# Adafruit_Feather_nRF52840_Sense_Rev_C.net
KiCad netlist of a schematic drawn in EAGLE
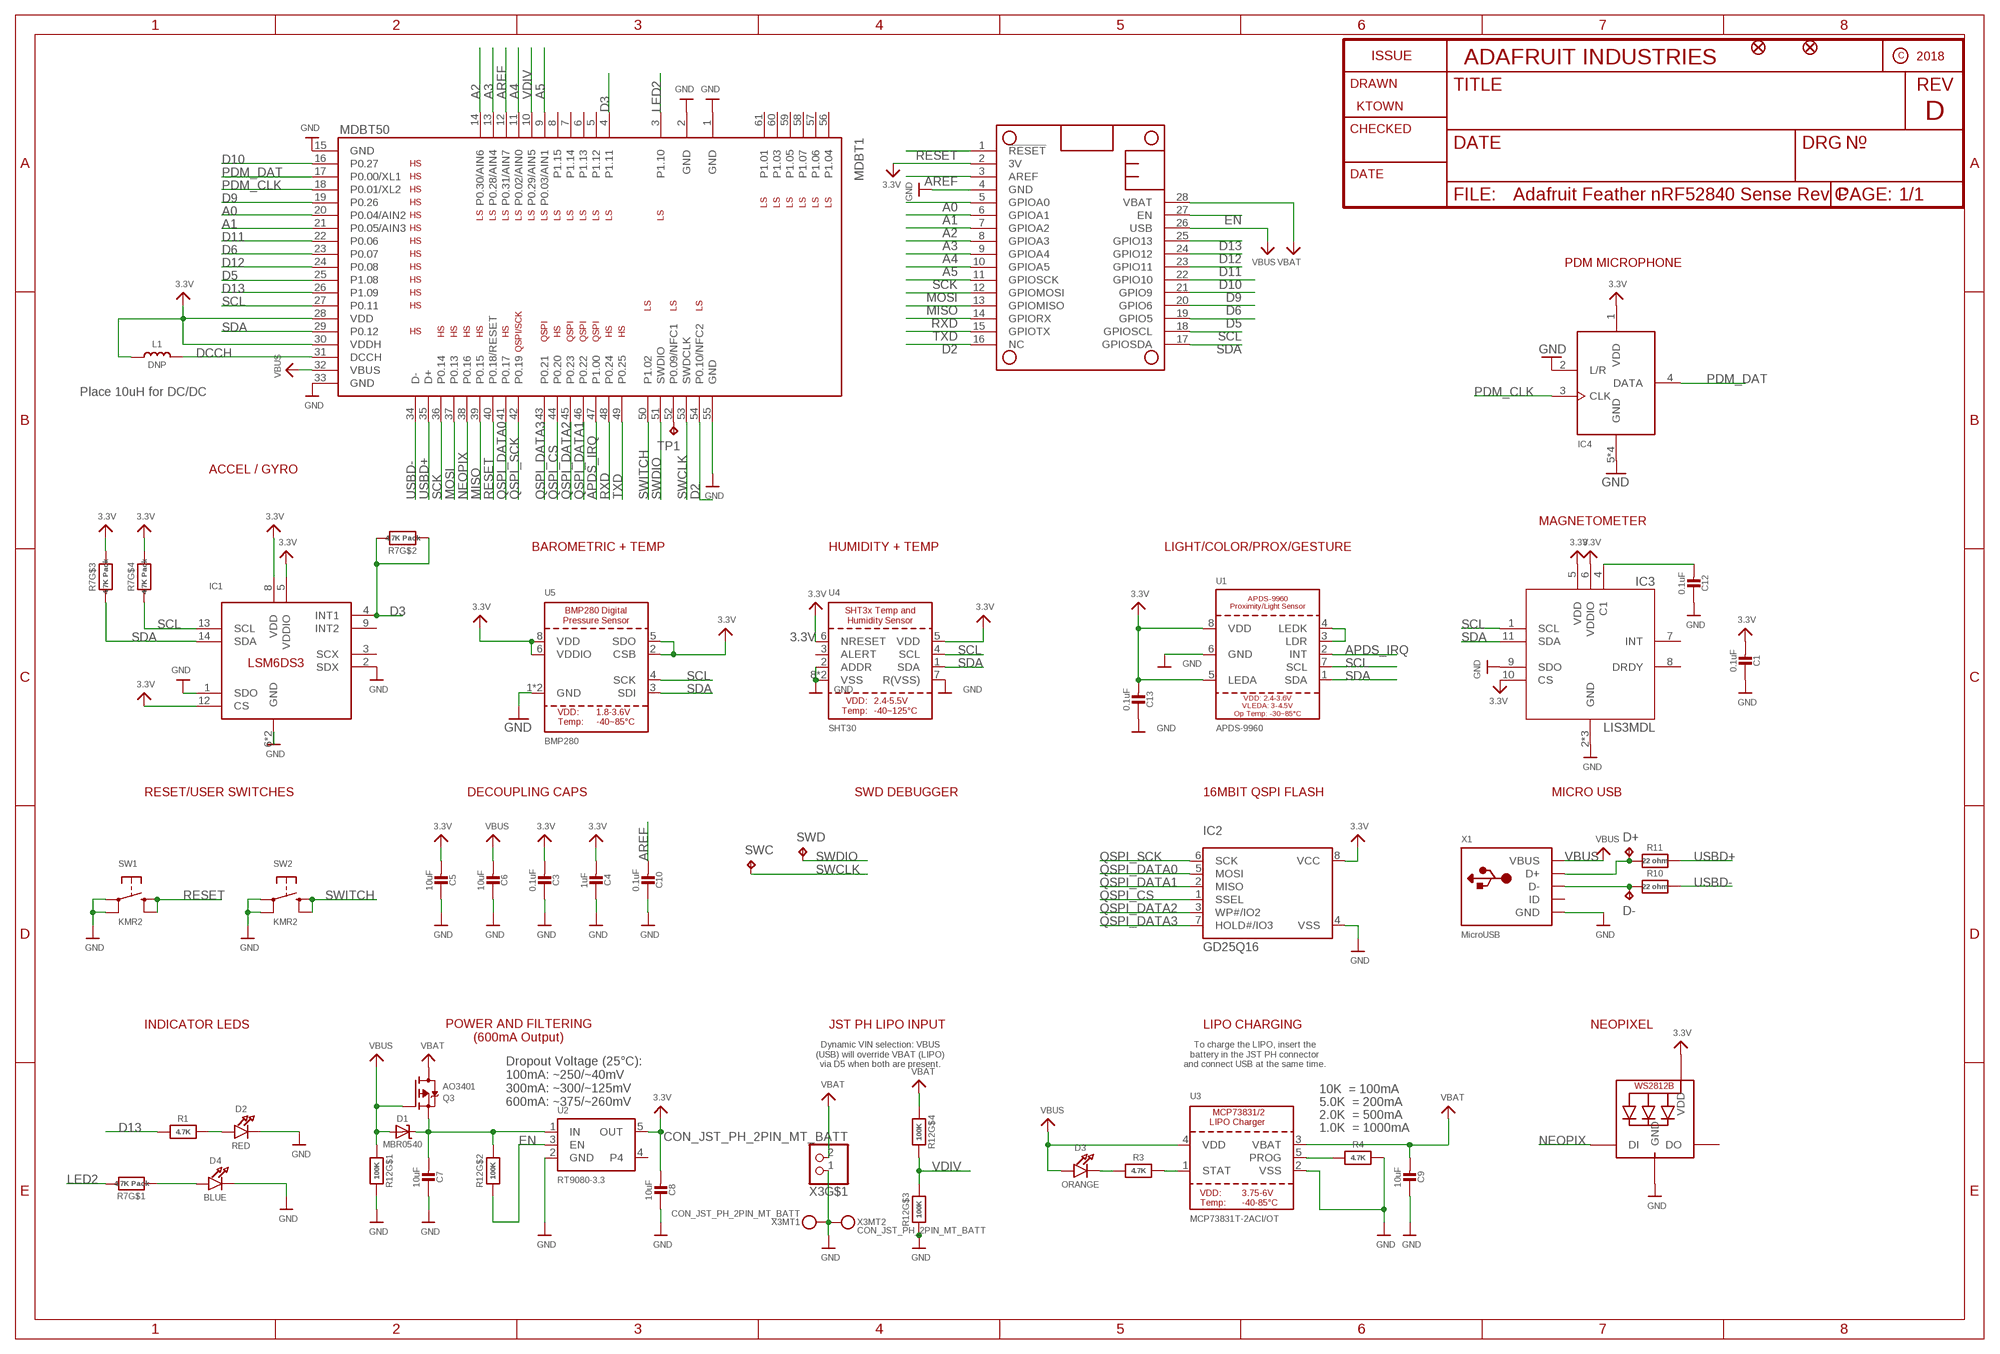
[diagram p0: schematic, sheet 1]

(export (version "E")
  (design (tool "Eeschema 10.0.6"))
  (components
    (comp (ref "C1")
      (value "0.1uF")
      (footprint "eagle-import:0603-NO")
      (libsource (lib "eagle-import") (part "CAP_CERAMIC0603_NO"))
    )
    (comp (ref "C3")
      (value "0.1uF")
      (footprint "eagle-import:0603-NO")
      (libsource (lib "eagle-import") (part "CAP_CERAMIC0603_NO"))
    )
    (comp (ref "C4")
      (value "1uF")
      (footprint "eagle-import:0603-NO")
      (libsource (lib "eagle-import") (part "CAP_CERAMIC0603_NO"))
    )
    (comp (ref "C5")
      (value "10uF")
      (footprint "eagle-import:0805-NO")
      (libsource (lib "eagle-import") (part "CAP_CERAMIC0805-NOOUTLINE"))
    )
    (comp (ref "C6")
      (value "10uF")
      (footprint "eagle-import:0805-NO")
      (libsource (lib "eagle-import") (part "CAP_CERAMIC0805-NOOUTLINE"))
    )
    (comp (ref "C7")
      (value "10uF")
      (footprint "eagle-import:0805-NO")
      (libsource (lib "eagle-import") (part "CAP_CERAMIC0805-NOOUTLINE"))
    )
    (comp (ref "C8")
      (value "10uF")
      (footprint "eagle-import:0805-NO")
      (libsource (lib "eagle-import") (part "CAP_CERAMIC0805-NOOUTLINE"))
    )
    (comp (ref "C9")
      (value "10uF")
      (footprint "eagle-import:0805-NO")
      (libsource (lib "eagle-import") (part "CAP_CERAMIC0805-NOOUTLINE"))
    )
    (comp (ref "C10")
      (value "0.1uF")
      (footprint "eagle-import:0603-NO")
      (libsource (lib "eagle-import") (part "CAP_CERAMIC0603_NO"))
    )
    (comp (ref "C12")
      (value "0.1uF")
      (footprint "eagle-import:0603-NO")
      (libsource (lib "eagle-import") (part "CAP_CERAMIC0603_NO"))
    )
    (comp (ref "C13")
      (value "0.1uF")
      (footprint "eagle-import:0603-NO")
      (libsource (lib "eagle-import") (part "CAP_CERAMIC0603_NO"))
    )
    (comp (ref "D+")
      (value "TPTP10R")
      (footprint "eagle-import:TP10R")
      (libsource (lib "eagle-import") (part "TPTP10R"))
    )
    (comp (ref "D-")
      (value "TPTP10R")
      (footprint "eagle-import:TP10R")
      (libsource (lib "eagle-import") (part "TPTP10R"))
    )
    (comp (ref "D1")
      (value "MBR0540")
      (footprint "eagle-import:SOD-123")
      (libsource (lib "eagle-import") (part "DIODE-SCHOTTKYSOD-123"))
    )
    (comp (ref "D2")
      (value "RED")
      (footprint "eagle-import:CHIPLED_0603_NOOUTLINE")
      (libsource (lib "eagle-import") (part "LED0603_NOOUTLINE"))
    )
    (comp (ref "D3")
      (value "ORANGE")
      (footprint "eagle-import:CHIPLED_0603_NOOUTLINE")
      (libsource (lib "eagle-import") (part "LED0603_NOOUTLINE"))
    )
    (comp (ref "D4")
      (value "BLUE")
      (footprint "eagle-import:CHIPLED_0603_NOOUTLINE")
      (libsource (lib "eagle-import") (part "LED0603_NOOUTLINE"))
    )
    (comp (ref "FID1")
      (value "FIDUCIAL_1MM")
      (footprint "eagle-import:FIDUCIAL_1MM")
      (libsource (lib "eagle-import") (part "FIDUCIAL_1MM"))
    )
    (comp (ref "FID2")
      (value "FIDUCIAL_1MM")
      (footprint "eagle-import:FIDUCIAL_1MM")
      (libsource (lib "eagle-import") (part "FIDUCIAL_1MM"))
    )
    (comp (ref "IC1")
      (value "LSM6DS3")
      (footprint "eagle-import:LGA-14L")
      (libsource (lib "eagle-import") (part "LSM6DS3"))
    )
    (comp (ref "IC2")
      (value "GD25Q16")
      (footprint "eagle-import:USON8")
      (libsource (lib "eagle-import") (part "SPIFLASH_8PINUX"))
    )
    (comp (ref "IC3")
      (value "LIS3MDL")
      (footprint "eagle-import:LGA12_2X2MM")
      (libsource (lib "eagle-import") (part "LIS3MDL"))
    )
    (comp (ref "IC4")
      (value "MIC_PDM")
      (footprint "eagle-import:SPK0415HM4H")
      (libsource (lib "eagle-import") (part "MIC_PDM_SPK0415"))
    )
    (comp (ref "L1")
      (value "DNP")
      (footprint "eagle-import:_0805MP")
      (libsource (lib "eagle-import") (part "INDUCTOR_0805MP"))
    )
    (comp (ref "LED1")
      (value "WS2812B_3535FULL")
      (footprint "eagle-import:LED3535_FULLPADS")
      (libsource (lib "eagle-import") (part "WS2812B_3535FULL"))
    )
    (comp (ref "MDBT1")
      (value "MDBT50")
      (footprint "eagle-import:MDBT50")
      (libsource (lib "eagle-import") (part "MDBT50"))
    )
    (comp (ref "MS1")
      (value "FEATHERWING_NODIM")
      (footprint "eagle-import:FEATHERWING_NODIM")
      (libsource (lib "eagle-import") (part "FEATHERWING_NODIM"))
    )
    (comp (ref "Q3")
      (value "AO3401")
      (footprint "eagle-import:SOT23-R")
      (libsource (lib "eagle-import") (part "MOSFET-P"))
    )
    (comp (ref "R1")
      (value "4.7K")
      (footprint "eagle-import:0603-NO")
      (libsource (lib "eagle-import") (part "RESISTOR_0603_NOOUT"))
    )
    (comp (ref "R3")
      (value "4.7K")
      (footprint "eagle-import:0603-NO")
      (libsource (lib "eagle-import") (part "RESISTOR_0603_NOOUT"))
    )
    (comp (ref "R4")
      (value "4.7K")
      (footprint "eagle-import:0603-NO")
      (libsource (lib "eagle-import") (part "RESISTOR_0603_NOOUT"))
    )
    (comp (ref "R7")
      (value "4.7K Pack")
      (footprint "eagle-import:RESPACK_4X0603")
      (libsource (lib "eagle-import") (part "RESISTOR_4PACK"))
    )
    (comp (ref "R10")
      (value "22 ohm")
      (footprint "eagle-import:0603-NO")
      (libsource (lib "eagle-import") (part "RESISTOR_0603_NOOUT"))
    )
    (comp (ref "R11")
      (value "22 ohm")
      (footprint "eagle-import:0603-NO")
      (libsource (lib "eagle-import") (part "RESISTOR_0603_NOOUT"))
    )
    (comp (ref "R12")
      (value "100K")
      (footprint "eagle-import:RESPACK_4X0603")
      (libsource (lib "eagle-import") (part "RESISTOR_4PACK"))
    )
    (comp (ref "SW1")
      (value "KMR2")
      (footprint "eagle-import:BTN_RKB2_4.6X2.8")
      (libsource (lib "eagle-import") (part "SWITCH_TACT_SMT_RKB2"))
    )
    (comp (ref "SW2")
      (value "KMR2")
      (footprint "eagle-import:BTN_RKB2_4.6X2.8")
      (libsource (lib "eagle-import") (part "SWITCH_TACT_SMT_RKB2"))
    )
    (comp (ref "SWC")
      (value "TPTP12R")
      (footprint "eagle-import:TP12R")
      (libsource (lib "eagle-import") (part "TPTP12R"))
    )
    (comp (ref "SWD")
      (value "TPTP12R")
      (footprint "eagle-import:TP12R")
      (libsource (lib "eagle-import") (part "TPTP12R"))
    )
    (comp (ref "TP1")
      (value "TPTP10R")
      (footprint "eagle-import:TP10R")
      (libsource (lib "eagle-import") (part "TPTP10R"))
    )
    (comp (ref "U1")
      (value "APDS-9960")
      (footprint "eagle-import:APDS-9960")
      (libsource (lib "eagle-import") (part "APDS-9960"))
    )
    (comp (ref "U2")
      (value "RT9080-3.3")
      (footprint "eagle-import:SOT23-5")
      (fields (field (name "JLC_ROTATION") "0"))
      (libsource (lib "eagle-import") (part "VREG_SOT23-5"))
    )
    (comp (ref "U3")
      (value "MCP73831T-2ACI/OT")
      (footprint "eagle-import:SOT23-5")
      (libsource (lib "eagle-import") (part "MCP73831/2"))
    )
    (comp (ref "U4")
      (value "SHT30")
      (footprint "eagle-import:SHT3X")
      (libsource (lib "eagle-import") (part "SHT3X"))
    )
    (comp (ref "U5")
      (value "BMP280")
      (footprint "eagle-import:BMP280")
      (libsource (lib "eagle-import") (part "BMP280"))
    )
    (comp (ref "X1")
      (value "MicroUSB")
      (footprint "eagle-import:4UCONN_20329_V2")
      (libsource (lib "eagle-import") (part "USB_MICRO_20329_V2"))
    )
    (comp (ref "X3")
      (value "CON_JST_PH_2PIN_MT_BATT")
      (footprint "eagle-import:JSTPH2_BATT")
      (libsource (lib "eagle-import") (part "CON_JST_PH_2PIN_MT_BATT"))
    )
  )
  (nets
    (net (code "1") (name "/A0") (class "Default")
      (node (ref "MDBT1") (pin "20") (pinfunction "P0.04/AIN2_20") (pintype "bidirectional"))
      (node (ref "MS1") (pin "5") (pinfunction "GPIOA0_5") (pintype "bidirectional"))
    )
    (net (code "2") (name "/A1") (class "Default")
      (node (ref "MDBT1") (pin "21") (pinfunction "P0.05/AIN3_21") (pintype "bidirectional"))
      (node (ref "MS1") (pin "6") (pinfunction "GPIOA1_6") (pintype "bidirectional"))
    )
    (net (code "3") (name "/A2") (class "Default")
      (node (ref "MDBT1") (pin "14") (pinfunction "P0.30/AIN6_14") (pintype "bidirectional"))
      (node (ref "MS1") (pin "7") (pinfunction "GPIOA2_7") (pintype "bidirectional"))
    )
    (net (code "4") (name "/A3") (class "Default")
      (node (ref "MDBT1") (pin "13") (pinfunction "P0.28/AIN4_13") (pintype "bidirectional"))
      (node (ref "MS1") (pin "8") (pinfunction "GPIOA3_8") (pintype "bidirectional"))
    )
    (net (code "5") (name "/A4") (class "Default")
      (node (ref "MDBT1") (pin "11") (pinfunction "P0.02/AIN0_11") (pintype "bidirectional"))
      (node (ref "MS1") (pin "9") (pinfunction "GPIOA4_9") (pintype "bidirectional"))
    )
    (net (code "6") (name "/A5") (class "Default")
      (node (ref "MDBT1") (pin "9") (pinfunction "P0.03/AIN1_9") (pintype "bidirectional"))
      (node (ref "MS1") (pin "10") (pinfunction "GPIOA5_10") (pintype "bidirectional"))
    )
    (net (code "7") (name "/APDS_IRQ") (class "Default")
      (node (ref "MDBT1") (pin "47") (pinfunction "P1.00_47") (pintype "bidirectional"))
      (node (ref "U1") (pin "2") (pinfunction "INT_2") (pintype "output"))
    )
    (net (code "8") (name "/AREF") (class "Default")
      (node (ref "C10") (pin "2") (pinfunction "2_2") (pintype "passive"))
      (node (ref "MDBT1") (pin "12") (pinfunction "P0.31/AIN7_12") (pintype "bidirectional"))
      (node (ref "MS1") (pin "3") (pinfunction "AREF_3") (pintype "passive"))
    )
    (net (code "9") (name "/D2") (class "Default")
      (node (ref "MDBT1") (pin "54") (pinfunction "P0.10/NFC2_54") (pintype "bidirectional"))
      (node (ref "MS1") (pin "16") (pinfunction "NC_16") (pintype "passive"))
    )
    (net (code "10") (name "/D3") (class "Default")
      (node (ref "IC1") (pin "4") (pinfunction "INT1_4") (pintype "bidirectional"))
      (node (ref "MDBT1") (pin "4") (pinfunction "P1.11_4") (pintype "bidirectional"))
      (node (ref "R7") (pin "2") (pinfunction "1_2") (pintype "passive"))
      (node (ref "R7") (pin "7") (pinfunction "2_7") (pintype "passive"))
    )
    (net (code "11") (name "/D5") (class "Default")
      (node (ref "MDBT1") (pin "25") (pinfunction "P1.08_25") (pintype "bidirectional"))
      (node (ref "MS1") (pin "19") (pinfunction "GPIO5_19") (pintype "bidirectional"))
    )
    (net (code "12") (name "/D6") (class "Default")
      (node (ref "MDBT1") (pin "23") (pinfunction "P0.07_23") (pintype "bidirectional"))
      (node (ref "MS1") (pin "20") (pinfunction "GPIO6_20") (pintype "bidirectional"))
    )
    (net (code "13") (name "/D9") (class "Default")
      (node (ref "MDBT1") (pin "19") (pinfunction "P0.26_19") (pintype "bidirectional"))
      (node (ref "MS1") (pin "21") (pinfunction "GPIO9_21") (pintype "bidirectional"))
    )
    (net (code "14") (name "/D10") (class "Default")
      (node (ref "MDBT1") (pin "16") (pinfunction "P0.27_16") (pintype "bidirectional"))
      (node (ref "MS1") (pin "22") (pinfunction "GPIO10_22") (pintype "bidirectional"))
    )
    (net (code "15") (name "/D11") (class "Default")
      (node (ref "MDBT1") (pin "22") (pinfunction "P0.06_22") (pintype "bidirectional"))
      (node (ref "MS1") (pin "23") (pinfunction "GPIO11_23") (pintype "bidirectional"))
    )
    (net (code "16") (name "/D12") (class "Default")
      (node (ref "MDBT1") (pin "24") (pinfunction "P0.08_24") (pintype "bidirectional"))
      (node (ref "MS1") (pin "24") (pinfunction "GPIO12_24") (pintype "bidirectional"))
    )
    (net (code "17") (name "/D13") (class "Default")
      (node (ref "MDBT1") (pin "26") (pinfunction "P1.09_26") (pintype "bidirectional"))
      (node (ref "MS1") (pin "25") (pinfunction "GPIO13_25") (pintype "bidirectional"))
      (node (ref "R1") (pin "1") (pinfunction "1_1") (pintype "passive"))
    )
    (net (code "18") (name "/DCCH") (class "Default")
      (node (ref "L1") (pin "2") (pinfunction "2_2") (pintype "passive"))
      (node (ref "MDBT1") (pin "31") (pinfunction "DCCH_31") (pintype "bidirectional"))
    )
    (net (code "19") (name "/EN") (class "Default")
      (node (ref "MS1") (pin "27") (pinfunction "EN_27") (pintype "passive"))
      (node (ref "R12") (pin "2") (pinfunction "1_2") (pintype "passive"))
      (node (ref "U2") (pin "3") (pinfunction "EN_3") (pintype "input"))
    )
    (net (code "20") (name "/LED2") (class "Default")
      (node (ref "MDBT1") (pin "3") (pinfunction "P1.10_3") (pintype "bidirectional"))
      (node (ref "R7") (pin "8") (pinfunction "2_8") (pintype "passive"))
    )
    (net (code "21") (name "/MISO") (class "Default")
      (node (ref "MDBT1") (pin "39") (pinfunction "P0.15_39") (pintype "bidirectional"))
      (node (ref "MS1") (pin "13") (pinfunction "GPIOMISO_13") (pintype "bidirectional"))
    )
    (net (code "22") (name "/MOSI") (class "Default")
      (node (ref "MDBT1") (pin "37") (pinfunction "P0.13_37") (pintype "bidirectional"))
      (node (ref "MS1") (pin "12") (pinfunction "GPIOMOSI_12") (pintype "bidirectional"))
    )
    (net (code "23") (name "/NEOPIX") (class "Default")
      (node (ref "LED1") (pin "1") (pinfunction "DI_1") (pintype "input"))
      (node (ref "MDBT1") (pin "38") (pinfunction "P0.16_38") (pintype "bidirectional"))
    )
    (net (code "24") (name "/PDM_CLK") (class "Default")
      (node (ref "IC4") (pin "3") (pinfunction "CLK_3") (pintype "input"))
      (node (ref "MDBT1") (pin "18") (pinfunction "P0.01/XL2_18") (pintype "bidirectional"))
    )
    (net (code "25") (name "/PDM_DAT") (class "Default")
      (node (ref "IC4") (pin "4") (pinfunction "DATA_4") (pintype "bidirectional"))
      (node (ref "MDBT1") (pin "17") (pinfunction "P0.00/XL1_17") (pintype "bidirectional"))
    )
    (net (code "26") (name "/QSPI_CS") (class "Default")
      (node (ref "IC2") (pin "1") (pinfunction "SSEL_1") (pintype "bidirectional"))
      (node (ref "MDBT1") (pin "44") (pinfunction "P0.20_44") (pintype "bidirectional"))
    )
    (net (code "27") (name "/QSPI_DATA0") (class "Default")
      (node (ref "IC2") (pin "5") (pinfunction "MOSI_5") (pintype "bidirectional"))
      (node (ref "MDBT1") (pin "41") (pinfunction "P0.17_41") (pintype "bidirectional"))
    )
    (net (code "28") (name "/QSPI_DATA1") (class "Default")
      (node (ref "IC2") (pin "2") (pinfunction "MISO_2") (pintype "bidirectional"))
      (node (ref "MDBT1") (pin "46") (pinfunction "P0.22_46") (pintype "bidirectional"))
    )
    (net (code "29") (name "/QSPI_DATA2") (class "Default")
      (node (ref "IC2") (pin "3") (pinfunction "WP#/IO2_3") (pintype "bidirectional"))
      (node (ref "MDBT1") (pin "45") (pinfunction "P0.23_45") (pintype "bidirectional"))
    )
    (net (code "30") (name "/QSPI_DATA3") (class "Default")
      (node (ref "IC2") (pin "7") (pinfunction "HOLD#/IO3_7") (pintype "bidirectional"))
      (node (ref "MDBT1") (pin "43") (pinfunction "P0.21_43") (pintype "bidirectional"))
    )
    (net (code "31") (name "/QSPI_SCK") (class "Default")
      (node (ref "IC2") (pin "6") (pinfunction "SCK_6") (pintype "bidirectional"))
      (node (ref "MDBT1") (pin "42") (pinfunction "P0.19_42") (pintype "bidirectional"))
    )
    (net (code "32") (name "/RESET") (class "Default")
      (node (ref "MDBT1") (pin "40") (pinfunction "P0.18/RESET_40") (pintype "bidirectional"))
      (node (ref "MS1") (pin "1") (pinfunction "~{RESET}_1") (pintype "input"))
      (node (ref "SW1") (pin "B") (pinfunction "S_B") (pintype "passive"))
      (node (ref "SW1") (pin "B'") (pinfunction "S1_B'") (pintype "passive"))
    )
    (net (code "33") (name "/RXD") (class "Default")
      (node (ref "MDBT1") (pin "48") (pinfunction "P0.24_48") (pintype "bidirectional"))
      (node (ref "MS1") (pin "14") (pinfunction "GPIORX_14") (pintype "bidirectional"))
    )
    (net (code "34") (name "/SCK") (class "Default")
      (node (ref "MDBT1") (pin "36") (pinfunction "P0.14_36") (pintype "bidirectional"))
      (node (ref "MS1") (pin "11") (pinfunction "GPIOSCK_11") (pintype "bidirectional"))
    )
    (net (code "35") (name "/SCL") (class "Default")
      (node (ref "IC1") (pin "13") (pinfunction "SCL_13") (pintype "bidirectional"))
      (node (ref "IC3") (pin "1") (pinfunction "SCL_1") (pintype "input"))
      (node (ref "MDBT1") (pin "27") (pinfunction "P0.11_27") (pintype "bidirectional"))
      (node (ref "MS1") (pin "18") (pinfunction "GPIOSCL_18") (pintype "bidirectional"))
      (node (ref "R7") (pin "4") (pinfunction "1_4") (pintype "passive"))
      (node (ref "U1") (pin "7") (pinfunction "SCL_7") (pintype "input"))
      (node (ref "U4") (pin "4") (pinfunction "SCL_4") (pintype "bidirectional"))
      (node (ref "U5") (pin "4") (pinfunction "SCK_4") (pintype "input"))
    )
    (net (code "36") (name "/SDA") (class "Default")
      (node (ref "IC1") (pin "14") (pinfunction "SDA_14") (pintype "bidirectional"))
      (node (ref "IC3") (pin "11") (pinfunction "SDA_11") (pintype "bidirectional"))
      (node (ref "MDBT1") (pin "29") (pinfunction "P0.12_29") (pintype "bidirectional"))
      (node (ref "MS1") (pin "17") (pinfunction "GPIOSDA_17") (pintype "bidirectional"))
      (node (ref "R7") (pin "3") (pinfunction "1_3") (pintype "passive"))
      (node (ref "U1") (pin "1") (pinfunction "SDA_1") (pintype "bidirectional"))
      (node (ref "U4") (pin "1") (pinfunction "SDA_1") (pintype "bidirectional"))
      (node (ref "U5") (pin "3") (pinfunction "SDI_3") (pintype "input"))
    )
    (net (code "37") (name "/SWCLK") (class "Default")
      (node (ref "MDBT1") (pin "53") (pinfunction "SWDCLK_53") (pintype "bidirectional"))
      (node (ref "SWC") (pin "TP") (pinfunction "TP_TP") (pintype "input"))
    )
    (net (code "38") (name "/SWDIO") (class "Default")
      (node (ref "MDBT1") (pin "51") (pinfunction "SWDIO_51") (pintype "bidirectional"))
      (node (ref "SWD") (pin "TP") (pinfunction "TP_TP") (pintype "input"))
    )
    (net (code "39") (name "/SWITCH") (class "Default")
      (node (ref "MDBT1") (pin "50") (pinfunction "P1.02_50") (pintype "bidirectional"))
      (node (ref "SW2") (pin "B") (pinfunction "S_B") (pintype "passive"))
      (node (ref "SW2") (pin "B'") (pinfunction "S1_B'") (pintype "passive"))
    )
    (net (code "40") (name "/TXD") (class "Default")
      (node (ref "MDBT1") (pin "49") (pinfunction "P0.25_49") (pintype "bidirectional"))
      (node (ref "MS1") (pin "15") (pinfunction "GPIOTX_15") (pintype "bidirectional"))
    )
    (net (code "41") (name "/USBD+") (class "Default")
      (node (ref "MDBT1") (pin "35") (pinfunction "D+_35") (pintype "bidirectional"))
      (node (ref "R11") (pin "2") (pinfunction "2_2") (pintype "passive"))
    )
    (net (code "42") (name "/USBD-") (class "Default")
      (node (ref "MDBT1") (pin "34") (pinfunction "D-_34") (pintype "bidirectional"))
      (node (ref "R10") (pin "2") (pinfunction "2_2") (pintype "passive"))
    )
    (net (code "43") (name "/VDIV") (class "Default")
      (node (ref "MDBT1") (pin "10") (pinfunction "P0.29/AIN5_10") (pintype "bidirectional"))
      (node (ref "R12") (pin "5") (pinfunction "2_5") (pintype "passive"))
      (node (ref "R12") (pin "6") (pinfunction "2_6") (pintype "passive"))
    )
    (net (code "44") (name "3.3V") (class "Default")
      (node (ref "C1") (pin "2") (pinfunction "2_2") (pintype "passive"))
      (node (ref "C13") (pin "2") (pinfunction "2_2") (pintype "passive"))
      (node (ref "C3") (pin "2") (pinfunction "2_2") (pintype "passive"))
      (node (ref "C4") (pin "2") (pinfunction "2_2") (pintype "passive"))
      (node (ref "C5") (pin "2") (pinfunction "2_2") (pintype "passive"))
      (node (ref "C8") (pin "2") (pinfunction "2_2") (pintype "passive"))
      (node (ref "IC1") (pin "12") (pinfunction "CS_12") (pintype "bidirectional"))
      (node (ref "IC1") (pin "5") (pinfunction "VDDIO_5") (pintype "power_in"))
      (node (ref "IC1") (pin "8") (pinfunction "VDD_8") (pintype "power_in"))
      (node (ref "IC2") (pin "8") (pinfunction "VCC_8") (pintype "bidirectional"))
      (node (ref "IC3") (pin "10") (pinfunction "CS_10") (pintype "input"))
      (node (ref "IC3") (pin "5") (pinfunction "VDD_5") (pintype "power_in"))
      (node (ref "IC3") (pin "6") (pinfunction "VDDIO_6") (pintype "power_in"))
      (node (ref "IC4") (pin "1") (pinfunction "VDD_1") (pintype "power_in"))
      (node (ref "L1") (pin "1") (pinfunction "1_1") (pintype "passive"))
      (node (ref "LED1") (pin "2") (pinfunction "VDD_2") (pintype "power_in"))
      (node (ref "MDBT1") (pin "28") (pinfunction "VDD_28") (pintype "bidirectional"))
      (node (ref "MDBT1") (pin "30") (pinfunction "VDDH_30") (pintype "bidirectional"))
      (node (ref "MS1") (pin "2") (pinfunction "3V_2") (pintype "power_in"))
      (node (ref "R7") (pin "5") (pinfunction "2_5") (pintype "passive"))
      (node (ref "R7") (pin "6") (pinfunction "2_6") (pintype "passive"))
      (node (ref "U1") (pin "5") (pinfunction "LEDA_5") (pintype "power_in"))
      (node (ref "U1") (pin "8") (pinfunction "VDD_8") (pintype "power_in"))
      (node (ref "U2") (pin "5") (pinfunction "OUT_5") (pintype "power_in"))
      (node (ref "U4") (pin "5") (pinfunction "VDD_5") (pintype "power_in"))
      (node (ref "U4") (pin "6") (pinfunction "NRESET_6") (pintype "bidirectional"))
      (node (ref "U5") (pin "2") (pinfunction "CSB_2") (pintype "input"))
      (node (ref "U5") (pin "5") (pinfunction "SDO_5") (pintype "output"))
      (node (ref "U5") (pin "6") (pinfunction "VDDIO_6") (pintype "power_in"))
      (node (ref "U5") (pin "8") (pinfunction "VDD_8") (pintype "power_in"))
    )
    (net (code "45") (name "GND") (class "Default")
      (node (ref "C1") (pin "1") (pinfunction "1_1") (pintype "passive"))
      (node (ref "C10") (pin "1") (pinfunction "1_1") (pintype "passive"))
      (node (ref "C12") (pin "1") (pinfunction "1_1") (pintype "passive"))
      (node (ref "C13") (pin "1") (pinfunction "1_1") (pintype "passive"))
      (node (ref "C3") (pin "1") (pinfunction "1_1") (pintype "passive"))
      (node (ref "C4") (pin "1") (pinfunction "1_1") (pintype "passive"))
      (node (ref "C5") (pin "1") (pinfunction "1_1") (pintype "passive"))
      (node (ref "C6") (pin "1") (pinfunction "1_1") (pintype "passive"))
      (node (ref "C7") (pin "1") (pinfunction "1_1") (pintype "passive"))
      (node (ref "C8") (pin "1") (pinfunction "1_1") (pintype "passive"))
      (node (ref "C9") (pin "1") (pinfunction "1_1") (pintype "passive"))
      (node (ref "D2") (pin "C") (pinfunction "C_C") (pintype "passive"))
      (node (ref "D4") (pin "C") (pinfunction "C_C") (pintype "passive"))
      (node (ref "IC1") (pin "1") (pinfunction "SDO_1") (pintype "bidirectional"))
      (node (ref "IC1") (pin "2") (pinfunction "SDX_2") (pintype "bidirectional"))
      (node (ref "IC1") (pin "6") (pinfunction "GND_6") (pintype "power_in"))
      (node (ref "IC1") (pin "7") (pinfunction "GND_7") (pintype "power_in"))
      (node (ref "IC2") (pin "4") (pinfunction "VSS_4") (pintype "bidirectional"))
      (node (ref "IC3") (pin "12") (pinfunction "GND_12") (pintype "power_in"))
      (node (ref "IC3") (pin "2") (pinfunction "GND_2") (pintype "power_in"))
      (node (ref "IC3") (pin "3") (pinfunction "GND_3") (pintype "power_in"))
      (node (ref "IC3") (pin "9") (pinfunction "SDO_9") (pintype "bidirectional"))
      (node (ref "IC4") (pin "2") (pinfunction "L/R_2") (pintype "input"))
      (node (ref "IC4") (pin "5") (pinfunction "GND_5") (pintype "power_in"))
      (node (ref "IC4") (pin "6") (pinfunction "GND_6") (pintype "power_in"))
      (node (ref "IC4") (pin "7") (pinfunction "GND_7") (pintype "power_in"))
      (node (ref "IC4") (pin "8") (pinfunction "GND_8") (pintype "power_in"))
      (node (ref "LED1") (pin "4") (pinfunction "GND_4") (pintype "power_in"))
      (node (ref "MDBT1") (pin "1") (pinfunction "GND_1") (pintype "bidirectional"))
      (node (ref "MDBT1") (pin "15") (pinfunction "GND_15") (pintype "bidirectional"))
      (node (ref "MDBT1") (pin "2") (pinfunction "GND_2") (pintype "bidirectional"))
      (node (ref "MDBT1") (pin "33") (pinfunction "GND_33") (pintype "bidirectional"))
      (node (ref "MDBT1") (pin "55") (pinfunction "GND_55") (pintype "bidirectional"))
      (node (ref "MS1") (pin "4") (pinfunction "GND_4") (pintype "power_in"))
      (node (ref "R12") (pin "3") (pinfunction "1_3") (pintype "passive"))
      (node (ref "R12") (pin "8") (pinfunction "2_8") (pintype "passive"))
      (node (ref "R4") (pin "2") (pinfunction "2_2") (pintype "passive"))
      (node (ref "SW1") (pin "A") (pinfunction "P_A") (pintype "passive"))
      (node (ref "SW1") (pin "A'") (pinfunction "P1_A'") (pintype "passive"))
      (node (ref "SW2") (pin "A") (pinfunction "P_A") (pintype "passive"))
      (node (ref "SW2") (pin "A'") (pinfunction "P1_A'") (pintype "passive"))
      (node (ref "U1") (pin "6") (pinfunction "GND_6") (pintype "power_in"))
      (node (ref "U2") (pin "2") (pinfunction "GND_2") (pintype "power_in"))
      (node (ref "U3") (pin "2") (pinfunction "VSS_2") (pintype "power_in"))
      (node (ref "U4") (pin "2") (pinfunction "ADDR_2") (pintype "bidirectional"))
      (node (ref "U4") (pin "7") (pinfunction "R(VSS)_7") (pintype "bidirectional"))
      (node (ref "U4") (pin "8") (pinfunction "VSS_8") (pintype "power_in"))
      (node (ref "U4") (pin "THERMAL") (pinfunction "VSS_THERMAL") (pintype "power_in"))
      (node (ref "U5") (pin "1") (pinfunction "GND_1") (pintype "power_in"))
      (node (ref "U5") (pin "7") (pinfunction "GND_7") (pintype "power_in"))
      (node (ref "X1") (pin "BASE@1") (pinfunction "GND_BASE@1") (pintype "power_in"))
      (node (ref "X1") (pin "BASE@2") (pinfunction "GND_BASE@2") (pintype "power_in"))
      (node (ref "X1") (pin "GND") (pinfunction "GND_GND") (pintype "power_in"))
      (node (ref "X1") (pin "SPRT@1") (pinfunction "GND_SPRT@1") (pintype "power_in"))
      (node (ref "X1") (pin "SPRT@2") (pinfunction "GND_SPRT@2") (pintype "power_in"))
      (node (ref "X1") (pin "SPRT@3") (pinfunction "GND_SPRT@3") (pintype "power_in"))
      (node (ref "X1") (pin "SPRT@4") (pinfunction "GND_SPRT@4") (pintype "power_in"))
      (node (ref "X3") (pin "1") (pinfunction "1_1") (pintype "passive"))
      (node (ref "X3") (pin "NC1") (pinfunction "P$1_NC1") (pintype "bidirectional"))
      (node (ref "X3") (pin "NC2") (pinfunction "P$1_NC2") (pintype "bidirectional"))
    )
    (net (code "46") (name "Net-(D+-PadTP)") (class "Default")
      (node (ref "D+") (pin "TP") (pinfunction "TP_TP") (pintype "input"))
      (node (ref "R11") (pin "1") (pinfunction "1_1") (pintype "passive"))
      (node (ref "X1") (pin "D+") (pinfunction "D+_D+") (pintype "bidirectional"))
    )
    (net (code "47") (name "Net-(D--PadTP)") (class "Default")
      (node (ref "D-") (pin "TP") (pinfunction "TP_TP") (pintype "input"))
      (node (ref "R10") (pin "1") (pinfunction "1_1") (pintype "passive"))
      (node (ref "X1") (pin "D-") (pinfunction "D-_D-") (pintype "bidirectional"))
    )
    (net (code "48") (name "Net-(D2-PadA)") (class "Default")
      (node (ref "D2") (pin "A") (pinfunction "A_A") (pintype "passive"))
      (node (ref "R1") (pin "2") (pinfunction "2_2") (pintype "passive"))
    )
    (net (code "49") (name "Net-(D3-PadC)") (class "Default")
      (node (ref "D3") (pin "C") (pinfunction "C_C") (pintype "passive"))
      (node (ref "R3") (pin "1") (pinfunction "1_1") (pintype "passive"))
    )
    (net (code "50") (name "Net-(D4-PadA)") (class "Default")
      (node (ref "D4") (pin "A") (pinfunction "A_A") (pintype "passive"))
      (node (ref "R7") (pin "1") (pinfunction "1_1") (pintype "passive"))
    )
    (net (code "51") (name "Net-(IC3-C1)") (class "Default")
      (node (ref "C12") (pin "2") (pinfunction "2_2") (pintype "passive"))
      (node (ref "IC3") (pin "4") (pinfunction "C1_4") (pintype "input"))
    )
    (net (code "52") (name "Net-(MDBT1-P0.09{slash}NFC1)") (class "Default")
      (node (ref "MDBT1") (pin "52") (pinfunction "P0.09/NFC1_52") (pintype "bidirectional"))
      (node (ref "TP1") (pin "TP") (pinfunction "TP_TP") (pintype "input"))
    )
    (net (code "53") (name "Net-(Q3-S)") (class "Default")
      (node (ref "C7") (pin "2") (pinfunction "2_2") (pintype "passive"))
      (node (ref "D1") (pin "C") (pinfunction "C_C") (pintype "passive"))
      (node (ref "Q3") (pin "2") (pinfunction "S_2") (pintype "passive"))
      (node (ref "R12") (pin "7") (pinfunction "2_7") (pintype "passive"))
      (node (ref "U2") (pin "1") (pinfunction "IN_1") (pintype "power_in"))
    )
    (net (code "54") (name "Net-(U1-LDR)") (class "Default")
      (node (ref "U1") (pin "3") (pinfunction "LDR_3") (pintype "bidirectional"))
      (node (ref "U1") (pin "4") (pinfunction "LEDK_4") (pintype "bidirectional"))
    )
    (net (code "55") (name "Net-(U3-PROG)") (class "Default")
      (node (ref "R4") (pin "1") (pinfunction "1_1") (pintype "passive"))
      (node (ref "U3") (pin "5") (pinfunction "PROG_5") (pintype "input"))
    )
    (net (code "56") (name "Net-(U3-STAT)") (class "Default")
      (node (ref "R3") (pin "2") (pinfunction "2_2") (pintype "passive"))
      (node (ref "U3") (pin "1") (pinfunction "STAT_1") (pintype "output"))
    )
    (net (code "57") (name "VBAT") (class "Default")
      (node (ref "C9") (pin "2") (pinfunction "2_2") (pintype "passive"))
      (node (ref "MS1") (pin "28") (pinfunction "VBAT_28") (pintype "power_in"))
      (node (ref "Q3") (pin "3") (pinfunction "D_3") (pintype "passive"))
      (node (ref "R12") (pin "4") (pinfunction "1_4") (pintype "passive"))
      (node (ref "U3") (pin "3") (pinfunction "VBAT_3") (pintype "power_in"))
      (node (ref "X3") (pin "2") (pinfunction "2_2") (pintype "passive"))
    )
    (net (code "58") (name "VBUS") (class "Default")
      (node (ref "C6") (pin "2") (pinfunction "2_2") (pintype "passive"))
      (node (ref "D1") (pin "A") (pinfunction "A_A") (pintype "passive"))
      (node (ref "D3") (pin "A") (pinfunction "A_A") (pintype "passive"))
      (node (ref "MDBT1") (pin "32") (pinfunction "VBUS_32") (pintype "bidirectional"))
      (node (ref "MS1") (pin "26") (pinfunction "USB_26") (pintype "power_in"))
      (node (ref "Q3") (pin "1") (pinfunction "G_1") (pintype "passive"))
      (node (ref "R12") (pin "1") (pinfunction "1_1") (pintype "passive"))
      (node (ref "U3") (pin "4") (pinfunction "VDD_4") (pintype "power_in"))
      (node (ref "X1") (pin "VBUS") (pinfunction "VBUS_VBUS") (pintype "power_in"))
    )
    (net (code "59") (name "unconnected-(IC1-INT2-Pad9)") (class "Default")
      (node (ref "IC1") (pin "9") (pinfunction "INT2_9") (pintype "bidirectional"))
    )
    (net (code "60") (name "unconnected-(IC1-SCX-Pad3)") (class "Default")
      (node (ref "IC1") (pin "3") (pinfunction "SCX_3") (pintype "bidirectional"))
    )
    (net (code "61") (name "unconnected-(IC3-DRDY-Pad8)") (class "Default")
      (node (ref "IC3") (pin "8") (pinfunction "DRDY_8") (pintype "output"))
    )
    (net (code "62") (name "unconnected-(IC3-INT-Pad7)") (class "Default")
      (node (ref "IC3") (pin "7") (pinfunction "INT_7") (pintype "output"))
    )
    (net (code "63") (name "unconnected-(LED1-DO-Pad3)") (class "Default")
      (node (ref "LED1") (pin "3") (pinfunction "DO_3") (pintype "output"))
    )
    (net (code "64") (name "unconnected-(MDBT1-P1.01-Pad61)") (class "Default")
      (node (ref "MDBT1") (pin "61") (pinfunction "P1.01_61") (pintype "bidirectional"))
    )
    (net (code "65") (name "unconnected-(MDBT1-P1.03-Pad60)") (class "Default")
      (node (ref "MDBT1") (pin "60") (pinfunction "P1.03_60") (pintype "bidirectional"))
    )
    (net (code "66") (name "unconnected-(MDBT1-P1.04-Pad56)") (class "Default")
      (node (ref "MDBT1") (pin "56") (pinfunction "P1.04_56") (pintype "bidirectional"))
    )
    (net (code "67") (name "unconnected-(MDBT1-P1.05-Pad59)") (class "Default")
      (node (ref "MDBT1") (pin "59") (pinfunction "P1.05_59") (pintype "bidirectional"))
    )
    (net (code "68") (name "unconnected-(MDBT1-P1.06-Pad57)") (class "Default")
      (node (ref "MDBT1") (pin "57") (pinfunction "P1.06_57") (pintype "bidirectional"))
    )
    (net (code "69") (name "unconnected-(MDBT1-P1.07-Pad58)") (class "Default")
      (node (ref "MDBT1") (pin "58") (pinfunction "P1.07_58") (pintype "bidirectional"))
    )
    (net (code "70") (name "unconnected-(MDBT1-P1.12-Pad5)") (class "Default")
      (node (ref "MDBT1") (pin "5") (pinfunction "P1.12_5") (pintype "bidirectional"))
    )
    (net (code "71") (name "unconnected-(MDBT1-P1.13-Pad6)") (class "Default")
      (node (ref "MDBT1") (pin "6") (pinfunction "P1.13_6") (pintype "bidirectional"))
    )
    (net (code "72") (name "unconnected-(MDBT1-P1.14-Pad7)") (class "Default")
      (node (ref "MDBT1") (pin "7") (pinfunction "P1.14_7") (pintype "bidirectional"))
    )
    (net (code "73") (name "unconnected-(MDBT1-P1.15-Pad8)") (class "Default")
      (node (ref "MDBT1") (pin "8") (pinfunction "P1.15_8") (pintype "bidirectional"))
    )
    (net (code "74") (name "unconnected-(U2-P4-Pad4)") (class "Default")
      (node (ref "U2") (pin "4") (pinfunction "P4_4") (pintype "bidirectional"))
    )
    (net (code "75") (name "unconnected-(U4-ALERT-Pad3)") (class "Default")
      (node (ref "U4") (pin "3") (pinfunction "ALERT_3") (pintype "bidirectional"))
    )
    (net (code "76") (name "unconnected-(X1-PadID)") (class "Default")
      (node (ref "X1") (pin "ID") (pinfunction "ID_ID") (pintype "bidirectional"))
    )
  )
)
